# Sheet1.net
KiCad netlist of a schematic drawn in Altium Designer
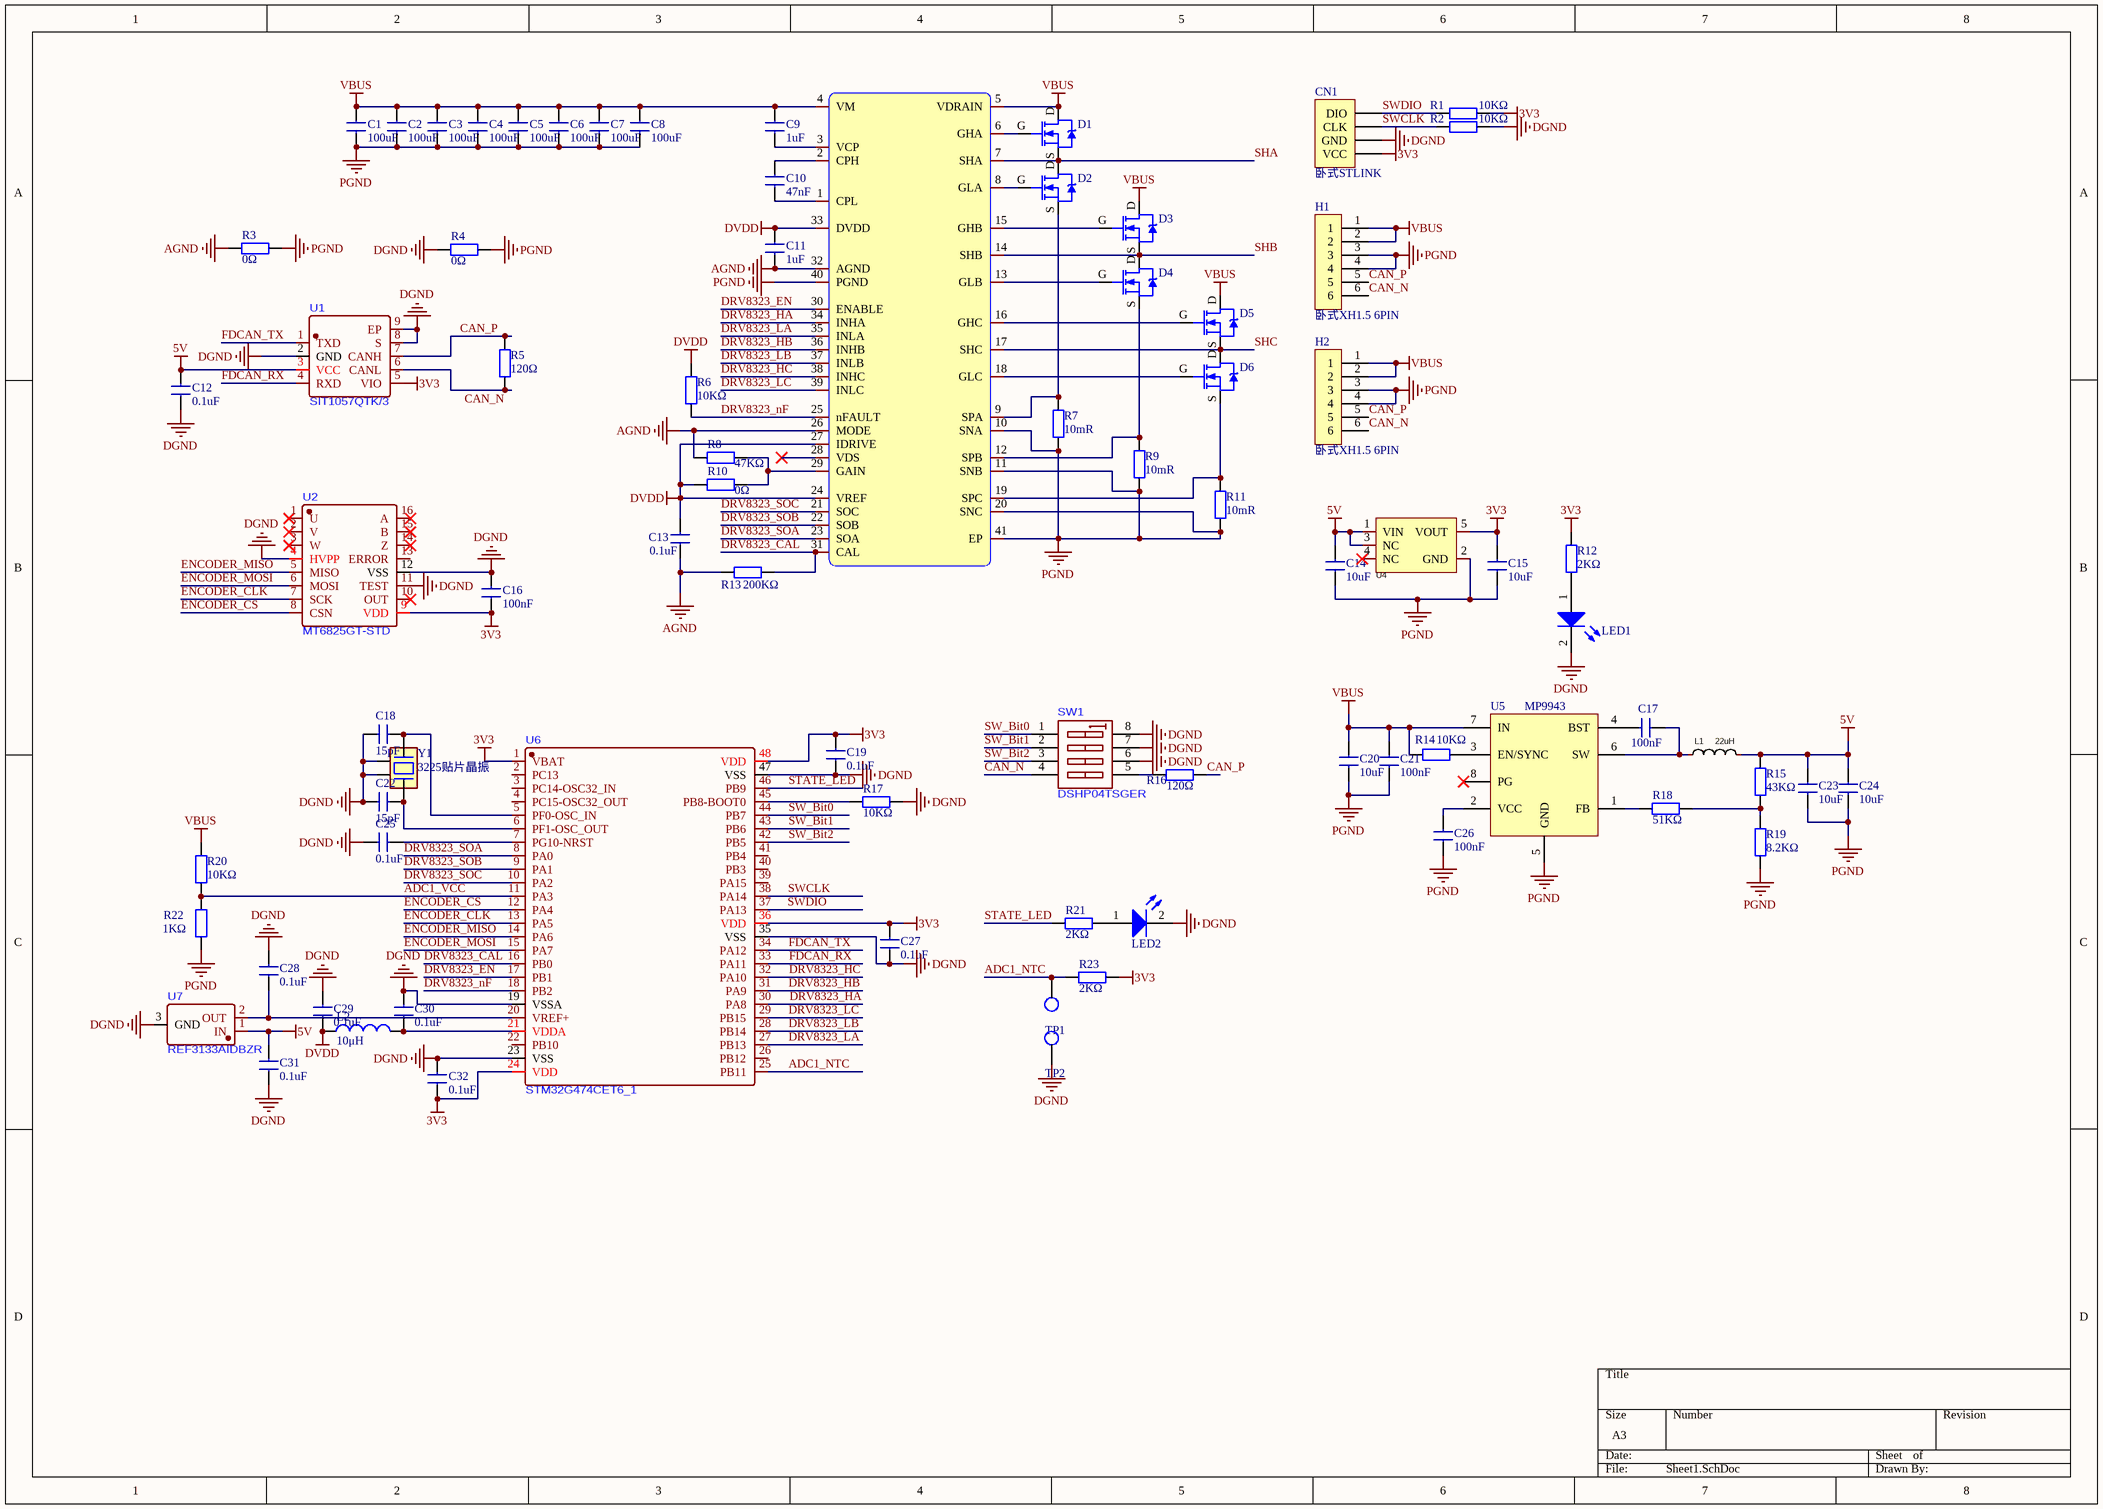
[diagram p0: Sheet1.SchDoc]

(export (version "E")
  (design (tool "Eeschema 10.0.6"))
  (components
    (comp (ref "C1")
      (value "100uF")
      (footprint "1206")
      (description "1210贴片电容")
      (libsource (lib "Integrated_Library1") (part "1210贴片电容"))
    )
    (comp (ref "C2")
      (value "100uF")
      (footprint "1206")
      (description "1210贴片电容")
      (libsource (lib "Integrated_Library1") (part "1210贴片电容"))
    )
    (comp (ref "C3")
      (value "100uF")
      (footprint "1206")
      (description "1210贴片电容")
      (libsource (lib "Integrated_Library1") (part "1210贴片电容"))
    )
    (comp (ref "C4")
      (value "100uF")
      (footprint "1206")
      (description "1210贴片电容")
      (libsource (lib "Integrated_Library1") (part "1210贴片电容"))
    )
    (comp (ref "C5")
      (value "100uF")
      (footprint "1206")
      (description "1210贴片电容")
      (libsource (lib "Integrated_Library1") (part "1210贴片电容"))
    )
    (comp (ref "C6")
      (value "100uF")
      (footprint "1206")
      (description "1210贴片电容")
      (libsource (lib "Integrated_Library1") (part "1210贴片电容"))
    )
    (comp (ref "C7")
      (value "100uF")
      (footprint "1206")
      (description "1210贴片电容")
      (libsource (lib "Integrated_Library1") (part "1210贴片电容"))
    )
    (comp (ref "C8")
      (value "100uF")
      (footprint "1206")
      (description "1210贴片电容")
      (libsource (lib "Integrated_Library1") (part "1210贴片电容"))
    )
    (comp (ref "C9")
      (value "1uF")
      (footprint "c0402")
      (description "贴片电容0402")
      (libsource (lib "Integrated_Library1") (part "0402贴片电容"))
    )
    (comp (ref "C10")
      (value "47nF")
      (footprint "c0402")
      (description "贴片电容0402")
      (libsource (lib "Integrated_Library1") (part "0402贴片电容"))
    )
    (comp (ref "C11")
      (value "1uF")
      (footprint "c0402")
      (description "贴片电容0402")
      (libsource (lib "Integrated_Library1") (part "0402贴片电容"))
    )
    (comp (ref "C12")
      (value "0.1uF")
      (footprint "c0402")
      (description "贴片电容0402")
      (libsource (lib "Integrated_Library1") (part "0402贴片电容"))
    )
    (comp (ref "C13")
      (value "0.1uF")
      (footprint "c0402")
      (description "贴片电容0402")
      (libsource (lib "Integrated_Library1") (part "0402贴片电容"))
    )
    (comp (ref "C14")
      (value "10uF")
      (footprint "c0402")
      (description "贴片电容0402")
      (libsource (lib "Integrated_Library1") (part "0402贴片电容"))
    )
    (comp (ref "C15")
      (value "10uF")
      (footprint "c0402")
      (description "贴片电容0402")
      (libsource (lib "Integrated_Library1") (part "0402贴片电容"))
    )
    (comp (ref "C16")
      (value "100nF")
      (footprint "C0402")
      (description "贴片电容0402")
      (libsource (lib "Integrated_Library1") (part "0402贴片电容"))
    )
    (comp (ref "C17")
      (value "100nF")
      (footprint "c0402")
      (description "贴片电容0402")
      (libsource (lib "Integrated_Library1") (part "0402贴片电容"))
    )
    (comp (ref "C18")
      (value "15pF")
      (footprint "c0402")
      (description "贴片电容0402")
      (libsource (lib "Integrated_Library1") (part "0402贴片电容"))
    )
    (comp (ref "C19")
      (value "0.1uF")
      (footprint "c0402")
      (description "贴片电容0402")
      (libsource (lib "Integrated_Library1") (part "0402贴片电容"))
    )
    (comp (ref "C20")
      (value "10uF")
      (footprint "C0603")
      (description "1210贴片电容")
      (libsource (lib "Integrated_Library1") (part "1210贴片电容"))
    )
    (comp (ref "C21")
      (value "100nF")
      (footprint "c0402")
      (description "贴片电容0402")
      (libsource (lib "Integrated_Library1") (part "0402贴片电容"))
    )
    (comp (ref "C22")
      (value "15pF")
      (footprint "c0402")
      (description "贴片电容0402")
      (libsource (lib "Integrated_Library1") (part "0402贴片电容"))
    )
    (comp (ref "C23")
      (value "10uF")
      (footprint "C0603")
      (description "1210贴片电容")
      (libsource (lib "Integrated_Library1") (part "1210贴片电容"))
    )
    (comp (ref "C24")
      (value "10uF")
      (footprint "C0603")
      (description "1210贴片电容")
      (libsource (lib "Integrated_Library1") (part "1210贴片电容"))
    )
    (comp (ref "C25")
      (value "0.1uF")
      (footprint "c0402")
      (description "贴片电容0402")
      (libsource (lib "Integrated_Library1") (part "0402贴片电容"))
    )
    (comp (ref "C26")
      (value "100nF")
      (footprint "c0402")
      (description "贴片电容0402")
      (libsource (lib "Integrated_Library1") (part "0402贴片电容"))
    )
    (comp (ref "C27")
      (value "0.1uF")
      (footprint "c0402")
      (description "贴片电容0402")
      (libsource (lib "Integrated_Library1") (part "0402贴片电容"))
    )
    (comp (ref "C28")
      (value "0.1uF")
      (footprint "c0402")
      (description "贴片电容0402")
      (libsource (lib "Integrated_Library1") (part "0402贴片电容"))
    )
    (comp (ref "C29")
      (value "0.1uF")
      (footprint "c0402")
      (description "贴片电容0402")
      (libsource (lib "Integrated_Library1") (part "0402贴片电容"))
    )
    (comp (ref "C30")
      (value "0.1uF")
      (footprint "c0402")
      (description "贴片电容0402")
      (libsource (lib "Integrated_Library1") (part "0402贴片电容"))
    )
    (comp (ref "C31")
      (value "0.1uF")
      (footprint "c0402")
      (description "贴片电容0402")
      (libsource (lib "Integrated_Library1") (part "0402贴片电容"))
    )
    (comp (ref "C32")
      (value "0.1uF")
      (footprint "c0402")
      (description "贴片电容0402")
      (libsource (lib "Integrated_Library1") (part "0402贴片电容"))
    )
    (comp (ref "CN1")
      (value "卧式STLINK")
      (footprint "CONN-SMD_4P-P1.25_GH1.25-4P")
      (libsource (lib "Integrated_Library1") (part "卧式STLINK"))
    )
    (comp (ref "D1")
      (value "NTMFS5C410NL")
      (footprint "DFN-8_L3.0-W3.0-P0.65-BL")
      (description "N沟道MOS管")
      (fields (field (name "PUBLISHER") "Altium Limited"))
      (libsource (lib "En") (part "NTMFS5C410NL"))
    )
    (comp (ref "D2")
      (value "NTMFS5C410NL")
      (footprint "DFN-8_L3.0-W3.0-P0.65-BL")
      (description "N沟道MOS管")
      (fields (field (name "PUBLISHER") "Altium Limited"))
      (libsource (lib "En") (part "NTMFS5C410NL"))
    )
    (comp (ref "D3")
      (value "NTMFS5C410NL")
      (footprint "DFN-8_L3.0-W3.0-P0.65-BL")
      (description "N沟道MOS管")
      (fields (field (name "PUBLISHER") "Altium Limited"))
      (libsource (lib "En") (part "NTMFS5C410NL"))
    )
    (comp (ref "D4")
      (value "NTMFS5C410NL")
      (footprint "DFN-8_L3.0-W3.0-P0.65-BL")
      (description "N沟道MOS管")
      (fields (field (name "PUBLISHER") "Altium Limited"))
      (libsource (lib "En") (part "NTMFS5C410NL"))
    )
    (comp (ref "D5")
      (value "NTMFS5C410NL")
      (footprint "DFN-8_L3.0-W3.0-P0.65-BL")
      (description "N沟道MOS管")
      (fields (field (name "PUBLISHER") "Altium Limited"))
      (libsource (lib "En") (part "NTMFS5C410NL"))
    )
    (comp (ref "D6")
      (value "NTMFS5C410NL")
      (footprint "DFN-8_L3.0-W3.0-P0.65-BL")
      (description "N沟道MOS管")
      (fields (field (name "PUBLISHER") "Altium Limited"))
      (libsource (lib "En") (part "NTMFS5C410NL"))
    )
    (comp (ref "H1")
      (value "卧式XH1.5 6PIN")
      (footprint "CONN-SMD_6P-P1.50_ZX-ZH1.5-6PWT")
      (libsource (lib "En") (part "卧式XH1.5 6PIN"))
    )
    (comp (ref "H2")
      (value "卧式XH1.5 6PIN")
      (footprint "CONN-SMD_6P-P1.50_ZX-ZH1.5-6PWT")
      (libsource (lib "En") (part "卧式XH1.5 6PIN"))
    )
    (comp (ref "L1")
      (value "22uH")
      (footprint "IND-SMD_L2.5-W2.0")
      (description "一体成型屏蔽电感，0530封装，额定电流3A")
      (fields (field (name "MANUFACTURER") "XR(祥如)") (field (name "MANUFACTURER PART") "XR0530-100M"))
      (libsource (lib "Integrated_Library1") (part "0530屏蔽电感"))
    )
    (comp (ref "L2")
      (value "10μH")
      (footprint "L0805")
      (description "0805贴片电感")
      (libsource (lib "Integrated_Library1") (part "0805贴片电感"))
    )
    (comp (ref "LED1")
      (value "LED")
      (footprint "led0805")
      (description "0805贴片LED")
      (libsource (lib "Integrated_Library1") (part "0805贴片LED"))
    )
    (comp (ref "LED2")
      (value "LED")
      (footprint "led0805")
      (description "0805贴片LED")
      (libsource (lib "Integrated_Library1") (part "0805贴片LED"))
    )
    (comp (ref "R1")
      (value "10KΩ")
      (footprint "R0402")
      (description "0402贴片电阻")
      (libsource (lib "") (part "0402贴片电阻_1"))
    )
    (comp (ref "R2")
      (value "10KΩ")
      (footprint "R0402")
      (description "0402贴片电阻")
      (libsource (lib "") (part "0402贴片电阻_1"))
    )
    (comp (ref "R3")
      (value "0Ω")
      (footprint "R0402")
      (description "0402贴片电阻")
      (libsource (lib "") (part "0402贴片电阻_1"))
    )
    (comp (ref "R4")
      (value "0Ω")
      (footprint "R0402")
      (description "0402贴片电阻")
      (libsource (lib "") (part "0402贴片电阻_1"))
    )
    (comp (ref "R5")
      (value "120Ω")
      (footprint "R0402")
      (description "0402贴片电阻")
      (libsource (lib "Integrated_Library1") (part "0402贴片电阻"))
    )
    (comp (ref "R6")
      (value "10KΩ")
      (footprint "R0402")
      (description "0402贴片电阻")
      (libsource (lib "Integrated_Library1") (part "0402贴片电阻"))
    )
    (comp (ref "R7")
      (value "10mR")
      (footprint "1206")
      (description "2512检流电阻")
      (libsource (lib "Integrated_Library1") (part "2512检流电阻"))
    )
    (comp (ref "R8")
      (value "47KΩ")
      (footprint "R0402")
      (description "0402贴片电阻")
      (libsource (lib "") (part "0402贴片电阻_1"))
    )
    (comp (ref "R9")
      (value "10mR")
      (footprint "1206")
      (description "2512检流电阻")
      (libsource (lib "Integrated_Library1") (part "2512检流电阻"))
    )
    (comp (ref "R10")
      (value "0Ω")
      (footprint "R0402")
      (description "0402贴片电阻")
      (libsource (lib "") (part "0402贴片电阻_1"))
    )
    (comp (ref "R11")
      (value "10mR")
      (footprint "1206")
      (description "2512检流电阻")
      (libsource (lib "Integrated_Library1") (part "2512检流电阻"))
    )
    (comp (ref "R12")
      (value "2KΩ")
      (footprint "R0402")
      (description "0402贴片电阻")
      (libsource (lib "Integrated_Library1") (part "0402贴片电阻"))
    )
    (comp (ref "R13")
      (value "200KΩ")
      (footprint "R0402")
      (description "0402贴片电阻")
      (libsource (lib "") (part "0402贴片电阻_3"))
    )
    (comp (ref "R14")
      (value "10KΩ")
      (footprint "R0402")
      (description "0402贴片电阻")
      (libsource (lib "") (part "0402贴片电阻_4"))
    )
    (comp (ref "R15")
      (value "43KΩ")
      (footprint "R0402")
      (description "0402贴片电阻")
      (libsource (lib "") (part "0402贴片电阻_5"))
    )
    (comp (ref "R16")
      (value "120Ω")
      (footprint "R0402")
      (description "0402贴片电阻")
      (libsource (lib "") (part "0402贴片电阻_3"))
    )
    (comp (ref "R17")
      (value "10KΩ")
      (footprint "R0402")
      (description "0402贴片电阻")
      (libsource (lib "") (part "0402贴片电阻_1"))
    )
    (comp (ref "R18")
      (value "51KΩ")
      (footprint "R0402")
      (description "0402贴片电阻")
      (libsource (lib "") (part "0402贴片电阻_4"))
    )
    (comp (ref "R19")
      (value "8.2KΩ")
      (footprint "R0402")
      (description "0402贴片电阻")
      (libsource (lib "") (part "0402贴片电阻_5"))
    )
    (comp (ref "R20")
      (value "10KΩ")
      (footprint "R0402")
      (description "0402贴片电阻")
      (libsource (lib "") (part "0402贴片电阻_2"))
    )
    (comp (ref "R21")
      (value "2KΩ")
      (footprint "R0402")
      (description "0402贴片电阻")
      (libsource (lib "") (part "0402贴片电阻_1"))
    )
    (comp (ref "R22")
      (value "1KΩ")
      (footprint "R0402")
      (description "0402贴片电阻")
      (libsource (lib "Integrated_Library1") (part "0402贴片电阻"))
    )
    (comp (ref "R23")
      (value "2KΩ")
      (footprint "R0402")
      (description "0402贴片电阻")
      (libsource (lib "") (part "0402贴片电阻_1"))
    )
    (comp (ref "SW1")
      (value "DSHP04TSGER")
      (footprint "SW-SMD_8P-L6.7-W5.4-P1.27-LS8.4")
      (libsource (lib "Integrated_Library1") (part "DSHP04TSGER"))
    )
    (comp (ref "TP1")
      (value "testpoint")
      (footprint "testpoint")
      (libsource (lib "Integrated_Library1") (part "testpoint"))
    )
    (comp (ref "TP2")
      (value "testpoint")
      (footprint "testpoint")
      (libsource (lib "Integrated_Library1") (part "testpoint"))
    )
    (comp (ref "U1")
      (value "SIT1057QTK/3")
      (footprint "DFN-8_L3.0-W3.0-P0.65-BL-EP")
      (libsource (lib "En") (part "SIT1057QTK/3"))
    )
    (comp (ref "U2")
      (value "MT6825GT-STD")
      (footprint "TSSOP-16_L5.0-W4.4-P0.65-LS6.4-BL-1")
      (description "18位绝对角编码器")
      (libsource (lib "Integrated_Library1") (part "MT6825GT-STD"))
    )
    (comp (ref "U3")
      (value "DRV8323HRTAR")
      (footprint "QFN-40_L6.0-W6.0-P0.50-BL-EP4.5")
      (fields (field (name "MANUFACTURER") "TI(德州仪器)"))
      (libsource (lib "Integrated_Library1") (part "DRV8323HRTAR"))
    )
    (comp (ref "U4")
      (value "XC6201P332MR-HXY")
      (footprint "SOT-23-5_L3.0-W1.7-P0.95-LS2.8-BR")
      (description "3.3V LDO")
      (fields (field (name "MANUFACTURER") "HXY MOSFET(华轩阳电子)"))
      (libsource (lib "Integrated_Library1") (part "XC6201P332MR-HXY"))
    )
    (comp (ref "U5")
      (value "MP9943")
      (footprint "QFN-8 3x3")
      (libsource (lib "Integrated_Library1") (part "MP9943"))
    )
    (comp (ref "U6")
      (value "STM32G474CET6_1")
      (footprint "LQFP-48_L7.0-W7.0-P0.50-LS9.0-BL")
      (libsource (lib "Integrated_Library1") (part "STM32G474CET6_1"))
    )
    (comp (ref "U7")
      (value "REF3133AIDBZR")
      (footprint "SOT-23-3_L2.9-W1.3-P1.90-LS2.4-BR")
      (libsource (lib "Integrated_Library1") (part "REF3133AIDBZR"))
    )
    (comp (ref "Y1")
      (value "3225贴片晶振")
      (footprint "OSC-3225-4P")
      (libsource (lib "Integrated_Library1") (part "3225贴片晶振"))
    )
  )
  (nets
    (net (code "1") (name "/ADC1_NTC") (class "Default")
      (node (ref "R23") (pin "1") (pinfunction "1_1") (pintype "passive"))
      (node (ref "TP1") (pin "1") (pinfunction "1_1") (pintype "passive"))
      (node (ref "U6") (pin "25") (pinfunction "PB11_25") (pintype "passive"))
    )
    (net (code "2") (name "/ADC1_VCC") (class "Default")
      (node (ref "R20") (pin "1") (pinfunction "1_1") (pintype "passive"))
      (node (ref "R22") (pin "1") (pinfunction "1_1") (pintype "passive"))
      (node (ref "U6") (pin "11") (pinfunction "PA3_11") (pintype "passive"))
    )
    (net (code "3") (name "/CAN_N") (class "Default")
      (node (ref "H1") (pin "6") (pinfunction "6_6") (pintype "passive"))
      (node (ref "H2") (pin "6") (pinfunction "6_6") (pintype "passive"))
      (node (ref "R5") (pin "2") (pinfunction "2_2") (pintype "passive"))
      (node (ref "SW1") (pin "4") (pinfunction "A4_4") (pintype "passive"))
      (node (ref "U1") (pin "6") (pinfunction "CANL_6") (pintype "passive"))
    )
    (net (code "4") (name "/CAN_P") (class "Default")
      (node (ref "H1") (pin "5") (pinfunction "5_5") (pintype "passive"))
      (node (ref "H2") (pin "5") (pinfunction "5_5") (pintype "passive"))
      (node (ref "R16") (pin "1") (pinfunction "1_1") (pintype "passive"))
      (node (ref "R5") (pin "1") (pinfunction "1_1") (pintype "passive"))
      (node (ref "U1") (pin "7") (pinfunction "CANH_7") (pintype "passive"))
    )
    (net (code "5") (name "/DRV8323_CAL") (class "Default")
      (node (ref "R13") (pin "1") (pinfunction "1_1") (pintype "passive"))
      (node (ref "U3") (pin "31") (pinfunction "CAL_31") (pintype "passive"))
      (node (ref "U6") (pin "16") (pinfunction "PB0_16") (pintype "passive"))
    )
    (net (code "6") (name "/DRV8323_EN") (class "Default")
      (node (ref "U3") (pin "30") (pinfunction "ENABLE_30") (pintype "passive"))
      (node (ref "U6") (pin "17") (pinfunction "PB1_17") (pintype "passive"))
    )
    (net (code "7") (name "/DRV8323_HA") (class "Default")
      (node (ref "U3") (pin "34") (pinfunction "INHA_34") (pintype "passive"))
      (node (ref "U6") (pin "30") (pinfunction "PA8_30") (pintype "passive"))
    )
    (net (code "8") (name "/DRV8323_HB") (class "Default")
      (node (ref "U3") (pin "36") (pinfunction "INHB_36") (pintype "passive"))
      (node (ref "U6") (pin "31") (pinfunction "PA9_31") (pintype "passive"))
    )
    (net (code "9") (name "/DRV8323_HC") (class "Default")
      (node (ref "U3") (pin "38") (pinfunction "INHC_38") (pintype "passive"))
      (node (ref "U6") (pin "32") (pinfunction "PA10_32") (pintype "passive"))
    )
    (net (code "10") (name "/DRV8323_LA") (class "Default")
      (node (ref "U3") (pin "35") (pinfunction "INLA_35") (pintype "passive"))
      (node (ref "U6") (pin "27") (pinfunction "PB13_27") (pintype "passive"))
    )
    (net (code "11") (name "/DRV8323_LB") (class "Default")
      (node (ref "U3") (pin "37") (pinfunction "INLB_37") (pintype "passive"))
      (node (ref "U6") (pin "28") (pinfunction "PB14_28") (pintype "passive"))
    )
    (net (code "12") (name "/DRV8323_LC") (class "Default")
      (node (ref "U3") (pin "39") (pinfunction "INLC_39") (pintype "passive"))
      (node (ref "U6") (pin "29") (pinfunction "PB15_29") (pintype "passive"))
    )
    (net (code "13") (name "/DRV8323_SOA") (class "Default")
      (node (ref "U3") (pin "23") (pinfunction "SOA_23") (pintype "passive"))
      (node (ref "U6") (pin "8") (pinfunction "PA0_8") (pintype "passive"))
    )
    (net (code "14") (name "/DRV8323_SOB") (class "Default")
      (node (ref "U3") (pin "22") (pinfunction "SOB_22") (pintype "passive"))
      (node (ref "U6") (pin "9") (pinfunction "PA1_9") (pintype "passive"))
    )
    (net (code "15") (name "/DRV8323_SOC") (class "Default")
      (node (ref "U3") (pin "21") (pinfunction "SOC_21") (pintype "passive"))
      (node (ref "U6") (pin "10") (pinfunction "PA2_10") (pintype "passive"))
    )
    (net (code "16") (name "/DRV8323_nF") (class "Default")
      (node (ref "R6") (pin "2") (pinfunction "2_2") (pintype "passive"))
      (node (ref "U3") (pin "25") (pinfunction "nFAULT_25") (pintype "passive"))
      (node (ref "U6") (pin "18") (pinfunction "PB2_18") (pintype "passive"))
    )
    (net (code "17") (name "/ENCODER_CLK") (class "Default")
      (node (ref "U2") (pin "7") (pinfunction "SCK_7") (pintype "passive"))
      (node (ref "U6") (pin "13") (pinfunction "PA5_13") (pintype "passive"))
    )
    (net (code "18") (name "/ENCODER_CS") (class "Default")
      (node (ref "U2") (pin "8") (pinfunction "CSN_8") (pintype "passive"))
      (node (ref "U6") (pin "12") (pinfunction "PA4_12") (pintype "passive"))
    )
    (net (code "19") (name "/ENCODER_MISO") (class "Default")
      (node (ref "U2") (pin "5") (pinfunction "MISO_5") (pintype "passive"))
      (node (ref "U6") (pin "14") (pinfunction "PA6_14") (pintype "passive"))
    )
    (net (code "20") (name "/ENCODER_MOSI") (class "Default")
      (node (ref "U2") (pin "6") (pinfunction "MOSI_6") (pintype "passive"))
      (node (ref "U6") (pin "15") (pinfunction "PA7_15") (pintype "passive"))
    )
    (net (code "21") (name "/FDCAN_RX") (class "Default")
      (node (ref "U1") (pin "4") (pinfunction "RXD_4") (pintype "passive"))
      (node (ref "U6") (pin "33") (pinfunction "PA11_33") (pintype "passive"))
    )
    (net (code "22") (name "/FDCAN_TX") (class "Default")
      (node (ref "U1") (pin "1") (pinfunction "TXD_1") (pintype "passive"))
      (node (ref "U6") (pin "34") (pinfunction "PA12_34") (pintype "passive"))
    )
    (net (code "23") (name "/SHA") (class "Default")
      (node (ref "D1") (pin "S") (pinfunction "S_S") (pintype "passive"))
      (node (ref "D2") (pin "D") (pinfunction "D_D") (pintype "passive"))
      (node (ref "U3") (pin "7") (pinfunction "SHA_7") (pintype "passive"))
    )
    (net (code "24") (name "/SHB") (class "Default")
      (node (ref "D3") (pin "S") (pinfunction "S_S") (pintype "passive"))
      (node (ref "D4") (pin "D") (pinfunction "D_D") (pintype "passive"))
      (node (ref "U3") (pin "14") (pinfunction "SHB_14") (pintype "passive"))
    )
    (net (code "25") (name "/SHC") (class "Default")
      (node (ref "D5") (pin "S") (pinfunction "S_S") (pintype "passive"))
      (node (ref "D6") (pin "D") (pinfunction "D_D") (pintype "passive"))
      (node (ref "U3") (pin "17") (pinfunction "SHC_17") (pintype "passive"))
    )
    (net (code "26") (name "/STATE_LED") (class "Default")
      (node (ref "R21") (pin "1") (pinfunction "1_1") (pintype "passive"))
      (node (ref "U6") (pin "46") (pinfunction "PB9_46") (pintype "passive"))
    )
    (net (code "27") (name "/SWCLK") (class "Default")
      (node (ref "CN1") (pin "3") (pinfunction "CLK_3") (pintype "passive"))
      (node (ref "R2") (pin "1") (pinfunction "1_1") (pintype "passive"))
      (node (ref "U6") (pin "38") (pinfunction "PA14_38") (pintype "passive"))
    )
    (net (code "28") (name "/SWDIO") (class "Default")
      (node (ref "CN1") (pin "4") (pinfunction "DIO_4") (pintype "passive"))
      (node (ref "R1") (pin "1") (pinfunction "1_1") (pintype "passive"))
      (node (ref "U6") (pin "37") (pinfunction "PA13_37") (pintype "passive"))
    )
    (net (code "29") (name "/SW_Bit0") (class "Default")
      (node (ref "SW1") (pin "1") (pinfunction "A1_1") (pintype "passive"))
      (node (ref "U6") (pin "44") (pinfunction "PB7_44") (pintype "passive"))
    )
    (net (code "30") (name "/SW_Bit1") (class "Default")
      (node (ref "SW1") (pin "2") (pinfunction "A2_2") (pintype "passive"))
      (node (ref "U6") (pin "43") (pinfunction "PB6_43") (pintype "passive"))
    )
    (net (code "31") (name "/SW_Bit2") (class "Default")
      (node (ref "SW1") (pin "3") (pinfunction "A3_3") (pintype "passive"))
      (node (ref "U6") (pin "42") (pinfunction "PB5_42") (pintype "passive"))
    )
    (net (code "32") (name "3V3") (class "Default")
      (node (ref "C15") (pin "2") (pinfunction "2_2") (pintype "passive"))
      (node (ref "C16") (pin "1") (pinfunction "1_1") (pintype "passive"))
      (node (ref "C19") (pin "1") (pinfunction "1_1") (pintype "passive"))
      (node (ref "C27") (pin "1") (pinfunction "1_1") (pintype "passive"))
      (node (ref "C32") (pin "2") (pinfunction "2_2") (pintype "passive"))
      (node (ref "CN1") (pin "1") (pinfunction "VCC_1") (pintype "passive"))
      (node (ref "R1") (pin "2") (pinfunction "2_2") (pintype "passive"))
      (node (ref "R12") (pin "1") (pinfunction "1_1") (pintype "passive"))
      (node (ref "R23") (pin "2") (pinfunction "2_2") (pintype "passive"))
      (node (ref "U1") (pin "5") (pinfunction "VIO_5") (pintype "passive"))
      (node (ref "U2") (pin "9") (pinfunction "VDD_9") (pintype "passive"))
      (node (ref "U4") (pin "5") (pinfunction "VOUT_5") (pintype "passive"))
      (node (ref "U6") (pin "1") (pinfunction "VBAT_1") (pintype "passive"))
      (node (ref "U6") (pin "24") (pinfunction "VDD_24") (pintype "passive"))
      (node (ref "U6") (pin "36") (pinfunction "VDD_36") (pintype "passive"))
      (node (ref "U6") (pin "48") (pinfunction "VDD_48") (pintype "passive"))
    )
    (net (code "33") (name "5V") (class "Default")
      (node (ref "C12") (pin "2") (pinfunction "2_2") (pintype "passive"))
      (node (ref "C14") (pin "2") (pinfunction "2_2") (pintype "passive"))
      (node (ref "C23") (pin "2") (pinfunction "2_2") (pintype "passive"))
      (node (ref "C24") (pin "2") (pinfunction "2_2") (pintype "passive"))
      (node (ref "C31") (pin "1") (pinfunction "1_1") (pintype "passive"))
      (node (ref "L1") (pin "2") (pinfunction "2_2") (pintype "passive"))
      (node (ref "R15") (pin "2") (pinfunction "2_2") (pintype "passive"))
      (node (ref "U1") (pin "3") (pinfunction "VCC_3") (pintype "passive"))
      (node (ref "U4") (pin "1") (pinfunction "VIN_1") (pintype "passive"))
      (node (ref "U4") (pin "3") (pinfunction "NC_3") (pintype "passive"))
      (node (ref "U7") (pin "1") (pinfunction "IN_1") (pintype "passive"))
    )
    (net (code "34") (name "AGND") (class "Default")
      (node (ref "C11") (pin "1") (pinfunction "1_1") (pintype "passive"))
      (node (ref "C13") (pin "1") (pinfunction "1_1") (pintype "passive"))
      (node (ref "R13") (pin "2") (pinfunction "2_2") (pintype "passive"))
      (node (ref "R3") (pin "1") (pinfunction "1_1") (pintype "passive"))
      (node (ref "R8") (pin "1") (pinfunction "1_1") (pintype "passive"))
      (node (ref "U3") (pin "26") (pinfunction "MODE_26") (pintype "passive"))
      (node (ref "U3") (pin "32") (pinfunction "AGND_32") (pintype "passive"))
    )
    (net (code "35") (name "DGND") (class "Default")
      (node (ref "C12") (pin "1") (pinfunction "1_1") (pintype "passive"))
      (node (ref "C16") (pin "2") (pinfunction "2_2") (pintype "passive"))
      (node (ref "C18") (pin "2") (pinfunction "2_2") (pintype "passive"))
      (node (ref "C19") (pin "2") (pinfunction "2_2") (pintype "passive"))
      (node (ref "C22") (pin "2") (pinfunction "2_2") (pintype "passive"))
      (node (ref "C25") (pin "2") (pinfunction "2_2") (pintype "passive"))
      (node (ref "C27") (pin "2") (pinfunction "2_2") (pintype "passive"))
      (node (ref "C28") (pin "2") (pinfunction "2_2") (pintype "passive"))
      (node (ref "C29") (pin "1") (pinfunction "1_1") (pintype "passive"))
      (node (ref "C30") (pin "1") (pinfunction "1_1") (pintype "passive"))
      (node (ref "C31") (pin "2") (pinfunction "2_2") (pintype "passive"))
      (node (ref "C32") (pin "1") (pinfunction "1_1") (pintype "passive"))
      (node (ref "CN1") (pin "2") (pinfunction "GND_2") (pintype "passive"))
      (node (ref "LED1") (pin "2") (pinfunction "K_2") (pintype "passive"))
      (node (ref "LED2") (pin "2") (pinfunction "K_2") (pintype "passive"))
      (node (ref "R17") (pin "2") (pinfunction "2_2") (pintype "passive"))
      (node (ref "R2") (pin "2") (pinfunction "2_2") (pintype "passive"))
      (node (ref "R4") (pin "1") (pinfunction "1_1") (pintype "passive"))
      (node (ref "SW1") (pin "6") (pinfunction "B3_6") (pintype "passive"))
      (node (ref "SW1") (pin "7") (pinfunction "B2_7") (pintype "passive"))
      (node (ref "SW1") (pin "8") (pinfunction "B1_8") (pintype "passive"))
      (node (ref "TP2") (pin "1") (pinfunction "1_1") (pintype "passive"))
      (node (ref "U1") (pin "2") (pinfunction "GND_2") (pintype "passive"))
      (node (ref "U1") (pin "8") (pinfunction "S_8") (pintype "passive"))
      (node (ref "U1") (pin "9") (pinfunction "EP_9") (pintype "passive"))
      (node (ref "U2") (pin "11") (pinfunction "TEST_11") (pintype "passive"))
      (node (ref "U2") (pin "12") (pinfunction "VSS_12") (pintype "passive"))
      (node (ref "U2") (pin "4") (pinfunction "HVPP_4") (pintype "passive"))
      (node (ref "U6") (pin "19") (pinfunction "VSSA_19") (pintype "passive"))
      (node (ref "U6") (pin "23") (pinfunction "VSS_23") (pintype "passive"))
      (node (ref "U6") (pin "35") (pinfunction "VSS_35") (pintype "passive"))
      (node (ref "U6") (pin "47") (pinfunction "VSS_47") (pintype "passive"))
      (node (ref "U7") (pin "3") (pinfunction "GND_3") (pintype "passive"))
      (node (ref "Y1") (pin "2") (pinfunction "2_2") (pintype "passive"))
      (node (ref "Y1") (pin "4") (pinfunction "4_4") (pintype "passive"))
    )
    (net (code "36") (name "DVDD") (class "Default")
      (node (ref "C11") (pin "2") (pinfunction "2_2") (pintype "passive"))
      (node (ref "C13") (pin "2") (pinfunction "2_2") (pintype "passive"))
      (node (ref "C29") (pin "2") (pinfunction "2_2") (pintype "passive"))
      (node (ref "L2") (pin "1") (pinfunction "1_1") (pintype "passive"))
      (node (ref "R10") (pin "1") (pinfunction "1_1") (pintype "passive"))
      (node (ref "R6") (pin "1") (pinfunction "1_1") (pintype "passive"))
      (node (ref "U3") (pin "24") (pinfunction "VREF_24") (pintype "passive"))
      (node (ref "U3") (pin "27") (pinfunction "IDRIVE_27") (pintype "passive"))
      (node (ref "U3") (pin "33") (pinfunction "DVDD_33") (pintype "passive"))
    )
    (net (code "37") (name "Net-(LED1-A)") (class "Default")
      (node (ref "LED1") (pin "1") (pinfunction "A_1") (pintype "passive"))
      (node (ref "R12") (pin "2") (pinfunction "2_2") (pintype "passive"))
    )
    (net (code "38") (name "Net-(LED2-A)") (class "Default")
      (node (ref "LED2") (pin "1") (pinfunction "A_1") (pintype "passive"))
      (node (ref "R21") (pin "2") (pinfunction "2_2") (pintype "passive"))
    )
    (net (code "39") (name "Net-(R15-Pad1)") (class "Default")
      (node (ref "R15") (pin "1") (pinfunction "1_1") (pintype "passive"))
      (node (ref "R18") (pin "2") (pinfunction "2_2") (pintype "passive"))
      (node (ref "R19") (pin "2") (pinfunction "2_2") (pintype "passive"))
    )
    (net (code "40") (name "Net-(SW1-B4)") (class "Default")
      (node (ref "R16") (pin "2") (pinfunction "2_2") (pintype "passive"))
      (node (ref "SW1") (pin "5") (pinfunction "B4_5") (pintype "passive"))
    )
    (net (code "41") (name "Net-(U3-CPH)") (class "Default")
      (node (ref "C10") (pin "2") (pinfunction "2_2") (pintype "passive"))
      (node (ref "U3") (pin "2") (pinfunction "CPH_2") (pintype "passive"))
    )
    (net (code "42") (name "Net-(U3-CPL)") (class "Default")
      (node (ref "C10") (pin "1") (pinfunction "1_1") (pintype "passive"))
      (node (ref "U3") (pin "1") (pinfunction "CPL_1") (pintype "passive"))
    )
    (net (code "43") (name "Net-(U3-GAIN)") (class "Default")
      (node (ref "R10") (pin "2") (pinfunction "2_2") (pintype "passive"))
      (node (ref "R8") (pin "2") (pinfunction "2_2") (pintype "passive"))
      (node (ref "U3") (pin "29") (pinfunction "GAIN_29") (pintype "passive"))
    )
    (net (code "44") (name "Net-(U3-GHA)") (class "Default")
      (node (ref "D1") (pin "G") (pinfunction "G_G") (pintype "passive"))
      (node (ref "U3") (pin "6") (pinfunction "GHA_6") (pintype "passive"))
    )
    (net (code "45") (name "Net-(U3-GHB)") (class "Default")
      (node (ref "D3") (pin "G") (pinfunction "G_G") (pintype "passive"))
      (node (ref "U3") (pin "15") (pinfunction "GHB_15") (pintype "passive"))
    )
    (net (code "46") (name "Net-(U3-GHC)") (class "Default")
      (node (ref "D5") (pin "G") (pinfunction "G_G") (pintype "passive"))
      (node (ref "U3") (pin "16") (pinfunction "GHC_16") (pintype "passive"))
    )
    (net (code "47") (name "Net-(U3-GLA)") (class "Default")
      (node (ref "D2") (pin "G") (pinfunction "G_G") (pintype "passive"))
      (node (ref "U3") (pin "8") (pinfunction "GLA_8") (pintype "passive"))
    )
    (net (code "48") (name "Net-(U3-GLB)") (class "Default")
      (node (ref "D4") (pin "G") (pinfunction "G_G") (pintype "passive"))
      (node (ref "U3") (pin "13") (pinfunction "GLB_13") (pintype "passive"))
    )
    (net (code "49") (name "Net-(U3-GLC)") (class "Default")
      (node (ref "D6") (pin "G") (pinfunction "G_G") (pintype "passive"))
      (node (ref "U3") (pin "18") (pinfunction "GLC_18") (pintype "passive"))
    )
    (net (code "50") (name "Net-(U3-SPA)") (class "Default")
      (node (ref "D2") (pin "S") (pinfunction "S_S") (pintype "passive"))
      (node (ref "R7") (pin "2") (pinfunction "2_2") (pintype "passive"))
      (node (ref "U3") (pin "9") (pinfunction "SPA_9") (pintype "passive"))
    )
    (net (code "51") (name "Net-(U3-SPB)") (class "Default")
      (node (ref "D4") (pin "S") (pinfunction "S_S") (pintype "passive"))
      (node (ref "R9") (pin "2") (pinfunction "2_2") (pintype "passive"))
      (node (ref "U3") (pin "12") (pinfunction "SPB_12") (pintype "passive"))
    )
    (net (code "52") (name "Net-(U3-SPC)") (class "Default")
      (node (ref "D6") (pin "S") (pinfunction "S_S") (pintype "passive"))
      (node (ref "R11") (pin "2") (pinfunction "2_2") (pintype "passive"))
      (node (ref "U3") (pin "19") (pinfunction "SPC_19") (pintype "passive"))
    )
    (net (code "53") (name "Net-(U3-VCP)") (class "Default")
      (node (ref "C9") (pin "1") (pinfunction "1_1") (pintype "passive"))
      (node (ref "U3") (pin "3") (pinfunction "VCP_3") (pintype "passive"))
    )
    (net (code "54") (name "Net-(U5-BST)") (class "Default")
      (node (ref "C17") (pin "1") (pinfunction "1_1") (pintype "passive"))
      (node (ref "U5") (pin "4") (pinfunction "BST_4") (pintype "passive"))
    )
    (net (code "55") (name "Net-(U5-EN{slash}SYNC)") (class "Default")
      (node (ref "R14") (pin "2") (pinfunction "2_2") (pintype "passive"))
      (node (ref "U5") (pin "3") (pinfunction "EN/SYNC_3") (pintype "passive"))
    )
    (net (code "56") (name "Net-(U5-FB)") (class "Default")
      (node (ref "R18") (pin "1") (pinfunction "1_1") (pintype "passive"))
      (node (ref "U5") (pin "1") (pinfunction "FB_1") (pintype "passive"))
    )
    (net (code "57") (name "Net-(U5-SW)") (class "Default")
      (node (ref "C17") (pin "2") (pinfunction "2_2") (pintype "passive"))
      (node (ref "L1") (pin "1") (pinfunction "1_1") (pintype "passive"))
      (node (ref "U5") (pin "6") (pinfunction "SW_6") (pintype "passive"))
    )
    (net (code "58") (name "Net-(U5-VCC)") (class "Default")
      (node (ref "C26") (pin "2") (pinfunction "2_2") (pintype "passive"))
      (node (ref "U5") (pin "2") (pinfunction "VCC_2") (pintype "passive"))
    )
    (net (code "59") (name "Net-(U6-PB8-BOOT0)") (class "Default")
      (node (ref "R17") (pin "1") (pinfunction "1_1") (pintype "passive"))
      (node (ref "U6") (pin "45") (pinfunction "PB8-BOOT0_45") (pintype "passive"))
    )
    (net (code "60") (name "Net-(U6-PF0-OSC_IN)") (class "Default")
      (node (ref "C18") (pin "1") (pinfunction "1_1") (pintype "passive"))
      (node (ref "U6") (pin "5") (pinfunction "PF0-OSC_IN_5") (pintype "passive"))
      (node (ref "Y1") (pin "3") (pinfunction "3_3") (pintype "passive"))
    )
    (net (code "61") (name "Net-(U6-PF1-OSC_OUT)") (class "Default")
      (node (ref "C22") (pin "1") (pinfunction "1_1") (pintype "passive"))
      (node (ref "U6") (pin "6") (pinfunction "PF1-OSC_OUT_6") (pintype "passive"))
      (node (ref "Y1") (pin "1") (pinfunction "1_1") (pintype "passive"))
    )
    (net (code "62") (name "Net-(U6-PG10-NRST)") (class "Default")
      (node (ref "C25") (pin "1") (pinfunction "1_1") (pintype "passive"))
      (node (ref "U6") (pin "7") (pinfunction "PG10-NRST_7") (pintype "passive"))
    )
    (net (code "63") (name "Net-(U6-VDDA)") (class "Default")
      (node (ref "C30") (pin "2") (pinfunction "2_2") (pintype "passive"))
      (node (ref "L2") (pin "2") (pinfunction "2_2") (pintype "passive"))
      (node (ref "U6") (pin "21") (pinfunction "VDDA_21") (pintype "passive"))
    )
    (net (code "64") (name "Net-(U6-VREF+)") (class "Default")
      (node (ref "C28") (pin "1") (pinfunction "1_1") (pintype "passive"))
      (node (ref "U6") (pin "20") (pinfunction "VREF+_20") (pintype "passive"))
      (node (ref "U7") (pin "2") (pinfunction "OUT_2") (pintype "passive"))
    )
    (net (code "65") (name "PGND") (class "Default")
      (node (ref "C1") (pin "1") (pinfunction "1_1") (pintype "passive"))
      (node (ref "C14") (pin "1") (pinfunction "1_1") (pintype "passive"))
      (node (ref "C15") (pin "1") (pinfunction "1_1") (pintype "passive"))
      (node (ref "C2") (pin "1") (pinfunction "1_1") (pintype "passive"))
      (node (ref "C20") (pin "1") (pinfunction "1_1") (pintype "passive"))
      (node (ref "C21") (pin "1") (pinfunction "1_1") (pintype "passive"))
      (node (ref "C23") (pin "1") (pinfunction "1_1") (pintype "passive"))
      (node (ref "C24") (pin "1") (pinfunction "1_1") (pintype "passive"))
      (node (ref "C26") (pin "1") (pinfunction "1_1") (pintype "passive"))
      (node (ref "C3") (pin "1") (pinfunction "1_1") (pintype "passive"))
      (node (ref "C4") (pin "1") (pinfunction "1_1") (pintype "passive"))
      (node (ref "C5") (pin "1") (pinfunction "1_1") (pintype "passive"))
      (node (ref "C6") (pin "1") (pinfunction "1_1") (pintype "passive"))
      (node (ref "C7") (pin "1") (pinfunction "1_1") (pintype "passive"))
      (node (ref "C8") (pin "1") (pinfunction "1_1") (pintype "passive"))
      (node (ref "H1") (pin "3") (pinfunction "3_3") (pintype "passive"))
      (node (ref "H1") (pin "4") (pinfunction "4_4") (pintype "passive"))
      (node (ref "H2") (pin "3") (pinfunction "3_3") (pintype "passive"))
      (node (ref "H2") (pin "4") (pinfunction "4_4") (pintype "passive"))
      (node (ref "R11") (pin "1") (pinfunction "1_1") (pintype "passive"))
      (node (ref "R19") (pin "1") (pinfunction "1_1") (pintype "passive"))
      (node (ref "R22") (pin "2") (pinfunction "2_2") (pintype "passive"))
      (node (ref "R3") (pin "2") (pinfunction "2_2") (pintype "passive"))
      (node (ref "R4") (pin "2") (pinfunction "2_2") (pintype "passive"))
      (node (ref "R7") (pin "1") (pinfunction "1_1") (pintype "passive"))
      (node (ref "R9") (pin "1") (pinfunction "1_1") (pintype "passive"))
      (node (ref "U3") (pin "10") (pinfunction "SNA_10") (pintype "passive"))
      (node (ref "U3") (pin "11") (pinfunction "SNB_11") (pintype "passive"))
      (node (ref "U3") (pin "20") (pinfunction "SNC_20") (pintype "passive"))
      (node (ref "U3") (pin "40") (pinfunction "PGND_40") (pintype "passive"))
      (node (ref "U3") (pin "41") (pinfunction "EP_41") (pintype "passive"))
      (node (ref "U4") (pin "2") (pinfunction "GND_2") (pintype "passive"))
      (node (ref "U5") (pin "5") (pinfunction "GND_5") (pintype "passive"))
    )
    (net (code "66") (name "VBUS") (class "Default")
      (node (ref "C1") (pin "2") (pinfunction "2_2") (pintype "passive"))
      (node (ref "C2") (pin "2") (pinfunction "2_2") (pintype "passive"))
      (node (ref "C20") (pin "2") (pinfunction "2_2") (pintype "passive"))
      (node (ref "C21") (pin "2") (pinfunction "2_2") (pintype "passive"))
      (node (ref "C3") (pin "2") (pinfunction "2_2") (pintype "passive"))
      (node (ref "C4") (pin "2") (pinfunction "2_2") (pintype "passive"))
      (node (ref "C5") (pin "2") (pinfunction "2_2") (pintype "passive"))
      (node (ref "C6") (pin "2") (pinfunction "2_2") (pintype "passive"))
      (node (ref "C7") (pin "2") (pinfunction "2_2") (pintype "passive"))
      (node (ref "C8") (pin "2") (pinfunction "2_2") (pintype "passive"))
      (node (ref "C9") (pin "2") (pinfunction "2_2") (pintype "passive"))
      (node (ref "D1") (pin "D") (pinfunction "D_D") (pintype "passive"))
      (node (ref "D3") (pin "D") (pinfunction "D_D") (pintype "passive"))
      (node (ref "D5") (pin "D") (pinfunction "D_D") (pintype "passive"))
      (node (ref "H1") (pin "1") (pinfunction "1_1") (pintype "passive"))
      (node (ref "H1") (pin "2") (pinfunction "2_2") (pintype "passive"))
      (node (ref "H2") (pin "1") (pinfunction "1_1") (pintype "passive"))
      (node (ref "H2") (pin "2") (pinfunction "2_2") (pintype "passive"))
      (node (ref "R14") (pin "1") (pinfunction "1_1") (pintype "passive"))
      (node (ref "R20") (pin "2") (pinfunction "2_2") (pintype "passive"))
      (node (ref "U3") (pin "4") (pinfunction "VM_4") (pintype "passive"))
      (node (ref "U3") (pin "5") (pinfunction "VDRAIN_5") (pintype "passive"))
      (node (ref "U5") (pin "7") (pinfunction "IN_7") (pintype "passive"))
    )
    (net (code "67") (name "unconnected-(U2-A-Pad16)") (class "Default")
      (node (ref "U2") (pin "16") (pinfunction "A_16") (pintype "passive+no_connect"))
    )
    (net (code "68") (name "unconnected-(U2-B-Pad15)") (class "Default")
      (node (ref "U2") (pin "15") (pinfunction "B_15") (pintype "passive+no_connect"))
    )
    (net (code "69") (name "unconnected-(U2-ERROR-Pad13)") (class "Default")
      (node (ref "U2") (pin "13") (pinfunction "ERROR_13") (pintype "passive"))
    )
    (net (code "70") (name "unconnected-(U2-OUT-Pad10)") (class "Default")
      (node (ref "U2") (pin "10") (pinfunction "OUT_10") (pintype "passive+no_connect"))
    )
    (net (code "71") (name "unconnected-(U2-U-Pad1)") (class "Default")
      (node (ref "U2") (pin "1") (pinfunction "U_1") (pintype "passive+no_connect"))
    )
    (net (code "72") (name "unconnected-(U2-V-Pad2)") (class "Default")
      (node (ref "U2") (pin "2") (pinfunction "V_2") (pintype "passive+no_connect"))
    )
    (net (code "73") (name "unconnected-(U2-W-Pad3)") (class "Default")
      (node (ref "U2") (pin "3") (pinfunction "W_3") (pintype "passive+no_connect"))
    )
    (net (code "74") (name "unconnected-(U2-Z-Pad14)") (class "Default")
      (node (ref "U2") (pin "14") (pinfunction "Z_14") (pintype "passive+no_connect"))
    )
    (net (code "75") (name "unconnected-(U3-VDS-Pad28)") (class "Default")
      (node (ref "U3") (pin "28") (pinfunction "VDS_28") (pintype "passive+no_connect"))
    )
    (net (code "76") (name "unconnected-(U4-NC-Pad4)") (class "Default")
      (node (ref "U4") (pin "4") (pinfunction "NC_4") (pintype "passive+no_connect"))
    )
    (net (code "77") (name "unconnected-(U5-PG-Pad8)") (class "Default")
      (node (ref "U5") (pin "8") (pinfunction "PG_8") (pintype "passive+no_connect"))
    )
    (net (code "78") (name "unconnected-(U6-PA15-Pad39)") (class "Default")
      (node (ref "U6") (pin "39") (pinfunction "PA15_39") (pintype "passive"))
    )
    (net (code "79") (name "unconnected-(U6-PB3-Pad40)") (class "Default")
      (node (ref "U6") (pin "40") (pinfunction "PB3_40") (pintype "passive"))
    )
    (net (code "80") (name "unconnected-(U6-PB4-Pad41)") (class "Default")
      (node (ref "U6") (pin "41") (pinfunction "PB4_41") (pintype "passive"))
    )
    (net (code "81") (name "unconnected-(U6-PB10-Pad22)") (class "Default")
      (node (ref "U6") (pin "22") (pinfunction "PB10_22") (pintype "passive"))
    )
    (net (code "82") (name "unconnected-(U6-PB12-Pad26)") (class "Default")
      (node (ref "U6") (pin "26") (pinfunction "PB12_26") (pintype "passive"))
    )
    (net (code "83") (name "unconnected-(U6-PC13-Pad2)") (class "Default")
      (node (ref "U6") (pin "2") (pinfunction "PC13_2") (pintype "passive"))
    )
    (net (code "84") (name "unconnected-(U6-PC14-OSC32_IN-Pad3)") (class "Default")
      (node (ref "U6") (pin "3") (pinfunction "PC14-OSC32_IN_3") (pintype "passive"))
    )
    (net (code "85") (name "unconnected-(U6-PC15-OSC32_OUT-Pad4)") (class "Default")
      (node (ref "U6") (pin "4") (pinfunction "PC15-OSC32_OUT_4") (pintype "passive"))
    )
  )
)
